# PressureSensors.net
KiCad netlist of a schematic drawn in EAGLE
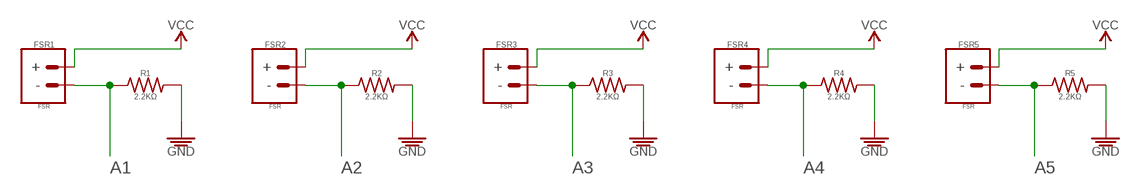
[diagram p0: schematic, sheet 1]

(export (version "E")
  (design (tool "Eeschema 10.0.6"))
  (components
    (comp (ref "FSR1")
      (value "FSR")
      (footprint "eagle-import:CONNECTOR_FSR")
      (fields
        (field (name "MFR") "Interlink Electronics")
        (field (name "MPN") "34-00004")
        (field (name "CREATOR") "MrSwirlyEyes")
      )
      (libsource (lib "eagle-import") (part "FSR_FORCE-SENSATIVE-RESISTOR_PRESS-SENSOR"))
    )
    (comp (ref "FSR2")
      (value "FSR")
      (footprint "eagle-import:CONNECTOR_FSR")
      (fields
        (field (name "MFR") "Interlink Electronics")
        (field (name "MPN") "34-00004")
        (field (name "CREATOR") "MrSwirlyEyes")
      )
      (libsource (lib "eagle-import") (part "FSR_FORCE-SENSATIVE-RESISTOR_PRESS-SENSOR"))
    )
    (comp (ref "FSR3")
      (value "FSR")
      (footprint "eagle-import:CONNECTOR_FSR")
      (fields
        (field (name "MFR") "Interlink Electronics")
        (field (name "MPN") "34-00004")
        (field (name "CREATOR") "MrSwirlyEyes")
      )
      (libsource (lib "eagle-import") (part "FSR_FORCE-SENSATIVE-RESISTOR_PRESS-SENSOR"))
    )
    (comp (ref "FSR4")
      (value "FSR")
      (footprint "eagle-import:CONNECTOR_FSR")
      (fields
        (field (name "MFR") "Interlink Electronics")
        (field (name "MPN") "34-00004")
        (field (name "CREATOR") "MrSwirlyEyes")
      )
      (libsource (lib "eagle-import") (part "FSR_FORCE-SENSATIVE-RESISTOR_PRESS-SENSOR"))
    )
    (comp (ref "FSR5")
      (value "FSR")
      (footprint "eagle-import:CONNECTOR_FSR")
      (fields
        (field (name "MFR") "Interlink Electronics")
        (field (name "MPN") "34-00004")
        (field (name "CREATOR") "MrSwirlyEyes")
      )
      (libsource (lib "eagle-import") (part "FSR_FORCE-SENSATIVE-RESISTOR_PRESS-SENSOR"))
    )
    (comp (ref "R1")
      (value "2.2KΩ")
      (footprint "eagle-import:RESISTOR_SMD-805")
      (fields
        (field (name "MFR") "Yageo")
        (field (name "MPN") "RC0805JR-072K2L")
        (field (name "CREATOR") "MrSwirlyEyes")
      )
      (libsource (lib "eagle-import") (part "2.2KΩ_SMD-0805_1/8W-5%"))
    )
    (comp (ref "R2")
      (value "2.2KΩ")
      (footprint "eagle-import:RESISTOR_SMD-805")
      (fields
        (field (name "MFR") "Yageo")
        (field (name "MPN") "RC0805JR-072K2L")
        (field (name "CREATOR") "MrSwirlyEyes")
      )
      (libsource (lib "eagle-import") (part "2.2KΩ_SMD-0805_1/8W-5%"))
    )
    (comp (ref "R3")
      (value "2.2KΩ")
      (footprint "eagle-import:RESISTOR_SMD-805")
      (fields
        (field (name "MFR") "Yageo")
        (field (name "MPN") "RC0805JR-072K2L")
        (field (name "CREATOR") "MrSwirlyEyes")
      )
      (libsource (lib "eagle-import") (part "2.2KΩ_SMD-0805_1/8W-5%"))
    )
    (comp (ref "R4")
      (value "2.2KΩ")
      (footprint "eagle-import:RESISTOR_SMD-805")
      (fields
        (field (name "MFR") "Yageo")
        (field (name "MPN") "RC0805JR-072K2L")
        (field (name "CREATOR") "MrSwirlyEyes")
      )
      (libsource (lib "eagle-import") (part "2.2KΩ_SMD-0805_1/8W-5%"))
    )
    (comp (ref "R5")
      (value "2.2KΩ")
      (footprint "eagle-import:RESISTOR_SMD-805")
      (fields
        (field (name "MFR") "Yageo")
        (field (name "MPN") "RC0805JR-072K2L")
        (field (name "CREATOR") "MrSwirlyEyes")
      )
      (libsource (lib "eagle-import") (part "2.2KΩ_SMD-0805_1/8W-5%"))
    )
  )
  (nets
    (net (code "1") (name "/A1") (class "Default")
      (node (ref "FSR1") (pin "-") (pinfunction "-_-") (pintype "passive"))
      (node (ref "R1") (pin "1") (pinfunction "1_1") (pintype "passive"))
    )
    (net (code "2") (name "/A2") (class "Default")
      (node (ref "FSR2") (pin "-") (pinfunction "-_-") (pintype "passive"))
      (node (ref "R2") (pin "1") (pinfunction "1_1") (pintype "passive"))
    )
    (net (code "3") (name "/A3") (class "Default")
      (node (ref "FSR3") (pin "-") (pinfunction "-_-") (pintype "passive"))
      (node (ref "R3") (pin "1") (pinfunction "1_1") (pintype "passive"))
    )
    (net (code "4") (name "/A4") (class "Default")
      (node (ref "FSR4") (pin "-") (pinfunction "-_-") (pintype "passive"))
      (node (ref "R4") (pin "1") (pinfunction "1_1") (pintype "passive"))
    )
    (net (code "5") (name "/A5") (class "Default")
      (node (ref "FSR5") (pin "-") (pinfunction "-_-") (pintype "passive"))
      (node (ref "R5") (pin "1") (pinfunction "1_1") (pintype "passive"))
    )
    (net (code "6") (name "GND") (class "Default")
      (node (ref "R1") (pin "2") (pinfunction "2_2") (pintype "passive"))
      (node (ref "R2") (pin "2") (pinfunction "2_2") (pintype "passive"))
      (node (ref "R3") (pin "2") (pinfunction "2_2") (pintype "passive"))
      (node (ref "R4") (pin "2") (pinfunction "2_2") (pintype "passive"))
      (node (ref "R5") (pin "2") (pinfunction "2_2") (pintype "passive"))
    )
    (net (code "7") (name "VCC") (class "Default")
      (node (ref "FSR1") (pin "+") (pinfunction "+_+") (pintype "passive"))
      (node (ref "FSR2") (pin "+") (pinfunction "+_+") (pintype "passive"))
      (node (ref "FSR3") (pin "+") (pinfunction "+_+") (pintype "passive"))
      (node (ref "FSR4") (pin "+") (pinfunction "+_+") (pintype "passive"))
      (node (ref "FSR5") (pin "+") (pinfunction "+_+") (pintype "passive"))
    )
  )
)
